# nRF24L01.net
KiCad netlist of a schematic drawn in Altium Designer
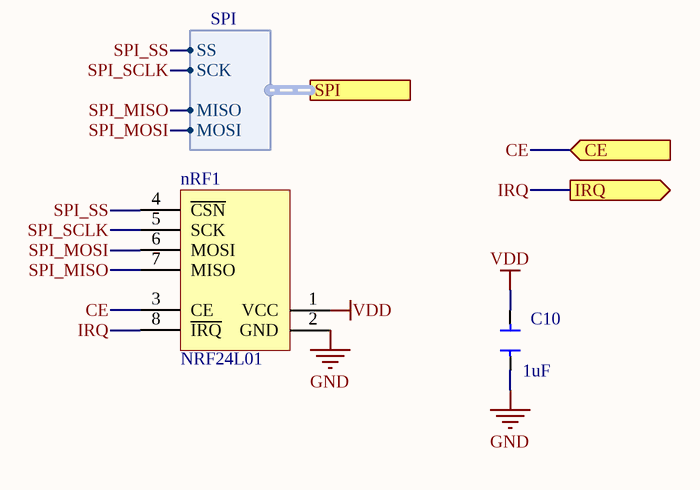
[diagram p0: nRF24L01.SchDoc]

(export (version "E")
  (design (tool "Eeschema 10.0.6"))
  (components
    (comp (ref "C10")
      (value "1uF")
      (footprint "Cap_0603")
      (fields (field (name "Comment") "Cap"))
      (libsource (lib "ZGR") (part "Cap"))
    )
    (comp (ref "nRF1")
      (value "NRF24L01")
      (footprint "NRF24L01P+PA+LNA+IPX")
      (libsource (lib "ZGR") (part "NRF24L01_module"))
    )
  )
  (nets
    (net (code "2") (name "/CE") (class "Default")
      (node (ref "nRF1") (pin "3") (pinfunction "CE_3") (pintype "passive"))
    )
    (net (code "3") (name "/IRQ") (class "Default")
      (node (ref "nRF1") (pin "8") (pinfunction "~{IRQ}_8") (pintype "passive"))
    )
    (net (code "4") (name "/SPI_MISO") (class "Default")
      (node (ref "nRF1") (pin "7") (pinfunction "MISO_7") (pintype "passive"))
    )
    (net (code "5") (name "/SPI_MOSI") (class "Default")
      (node (ref "nRF1") (pin "6") (pinfunction "MOSI_6") (pintype "passive"))
    )
    (net (code "6") (name "/SPI_SCLK") (class "Default")
      (node (ref "nRF1") (pin "5") (pinfunction "SCK_5") (pintype "passive"))
    )
    (net (code "7") (name "/SPI_SS") (class "Default")
      (node (ref "nRF1") (pin "4") (pinfunction "~{CSN}_4") (pintype "passive"))
    )
    (net (code "9") (name "GND") (class "Default")
      (node (ref "C10") (pin "2") (pinfunction "2_2") (pintype "passive"))
      (node (ref "nRF1") (pin "2") (pinfunction "GND_2") (pintype "power_in"))
    )
    (net (code "10") (name "VDD") (class "Default")
      (node (ref "C10") (pin "1") (pinfunction "1_1") (pintype "passive"))
      (node (ref "nRF1") (pin "1") (pinfunction "VCC_1") (pintype "power_in"))
    )
  )
)
